# QSPI.net
KiCad netlist of a schematic drawn in Altium Designer
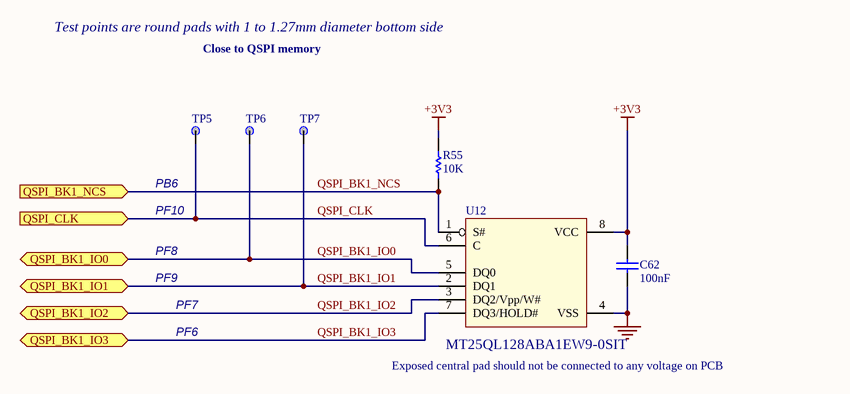
[diagram p0: QSPI.SchDoc]

(export (version "E")
  (design (tool "Eeschema 10.0.6"))
  (components
    (comp (ref "C62")
      (value "100nF")
      (footprint "0402C")
      (description "Capacitor")
      (fields (field (name "PUBLISHER") "Altium Limited"))
      (libsource (lib "Miscellaneous Devices") (part "Cap"))
    )
    (comp (ref "R55")
      (value "10K")
      (footprint "0402R")
      (description "Resistor")
      (libsource (lib "MCD_TOOLS") (part "Res_10K_1%_0402"))
    )
    (comp (ref "TP5") (value "TP") (footprint "TP_C40") (libsource (lib "Almos") (part "TP")))
    (comp (ref "TP6") (value "TP") (footprint "TP_C40") (libsource (lib "Almos") (part "TP")))
    (comp (ref "TP7") (value "TP") (footprint "TP_C40") (libsource (lib "Almos") (part "TP")))
    (comp (ref "U12")
      (value "MT25QL128ABA1EW9-0SIT")
      (footprint "DFN8_1R27_6X8_TP4R8X5R8")
      (description "128Mb, 3V, Multiple I/O Serial Flash Memory, Quad/Dual")
      (libsource (lib "MCD_TOOLS") (part "N25Q128A13EF840E"))
    )
  )
  (nets
    (net (code "1") (name "+3V3") (class "Default")
      (node (ref "C62") (pin "1") (pinfunction "1_1") (pintype "passive"))
      (node (ref "R55") (pin "2") (pinfunction "2_2") (pintype "passive"))
      (node (ref "U12") (pin "8") (pinfunction "VCC_8") (pintype "passive"))
    )
    (net (code "2") (name "/QSPI_BK1_IO0") (class "Default")
      (node (ref "TP6") (pin "1") (pinfunction "1_1") (pintype "passive"))
      (node (ref "U12") (pin "5") (pinfunction "DQ0_5") (pintype "passive"))
    )
    (net (code "3") (name "/QSPI_BK1_IO1") (class "Default")
      (node (ref "TP7") (pin "1") (pinfunction "1_1") (pintype "passive"))
      (node (ref "U12") (pin "2") (pinfunction "DQ1_2") (pintype "passive"))
    )
    (net (code "4") (name "/QSPI_BK1_IO2") (class "Default")
      (node (ref "U12") (pin "3") (pinfunction "DQ2/Vpp/W#_3") (pintype "passive"))
    )
    (net (code "5") (name "/QSPI_BK1_IO3") (class "Default")
      (node (ref "U12") (pin "7") (pinfunction "DQ3/HOLD#_7") (pintype "passive"))
    )
    (net (code "6") (name "/QSPI_BK1_NCS") (class "Default")
      (node (ref "R55") (pin "1") (pinfunction "1_1") (pintype "passive"))
      (node (ref "U12") (pin "1") (pinfunction "S#_1") (pintype "passive"))
    )
    (net (code "7") (name "/QSPI_CLK") (class "Default")
      (node (ref "TP5") (pin "1") (pinfunction "1_1") (pintype "passive"))
      (node (ref "U12") (pin "6") (pinfunction "C_6") (pintype "passive"))
    )
    (net (code "8") (name "GND") (class "Default")
      (node (ref "C62") (pin "2") (pinfunction "2_2") (pintype "passive"))
      (node (ref "U12") (pin "4") (pinfunction "VSS_4") (pintype "passive"))
    )
  )
)
